# ESP32_garage_door.net
KiCad netlist of a schematic drawn in Altium Designer
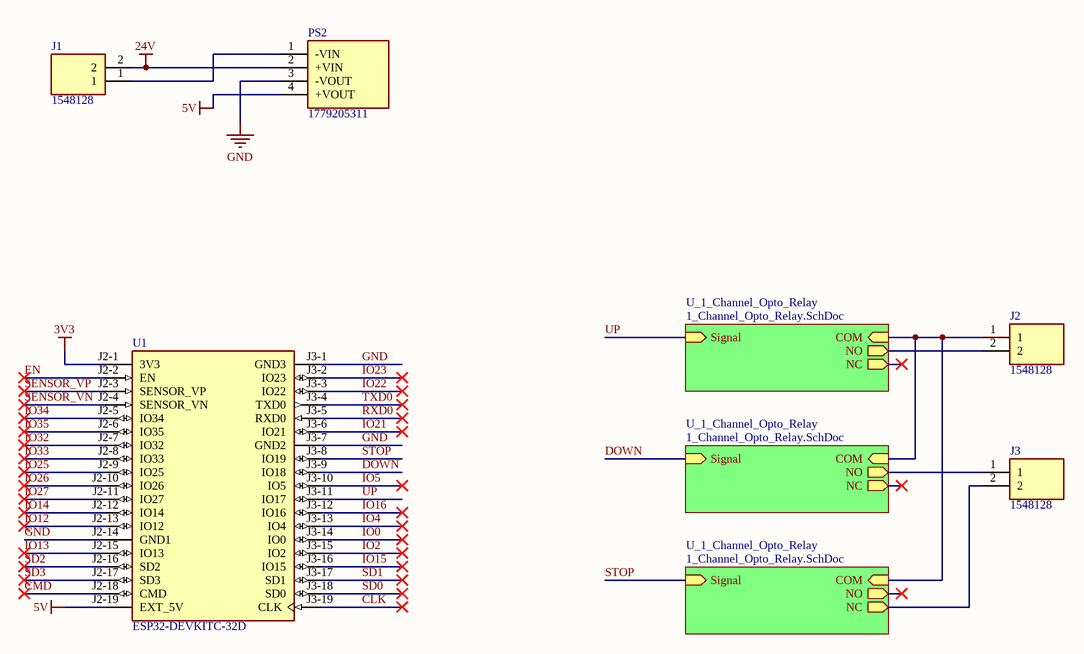
[diagram p0: ESP32_garage_door.SchDoc]

(export (version "E")
  (design (tool "Eeschema 10.0.6"))
  (components
    (comp (ref "J1")
      (value "1548128")
      (footprint "SamacSys:1548128")
      (description "Connector")
      (fields (field (name "MOUSER PART NUMBER") "651-1548128"))
      (libsource (lib "") (part "1548128_1"))
    )
    (comp (ref "J2")
      (value "1548128")
      (footprint "SamacSys:1548128")
      (description "Connector")
      (fields (field (name "MOUSER PART NUMBER") "651-1548128"))
      (libsource (lib "*") (part "1548128"))
    )
    (comp (ref "J3")
      (value "1548128")
      (footprint "SamacSys:1548128")
      (description "Connector")
      (fields (field (name "MOUSER PART NUMBER") "651-1548128"))
      (libsource (lib "*") (part "1548128"))
    )
    (comp (ref "PS2")
      (value "1779205311")
      (footprint "SamacSys:1779205311")
      (description "Power Supply")
      (libsource (lib "*") (part "1779205311"))
    )
    (comp (ref "U1")
      (value "ESP32-DEVKITC-32D")
      (footprint "MODULE_ESP32-DEVKITC-32D")
      (description "WiFi Development Tools (802.11) ESP32 General Development Kit, ESP32-WROOM-32D on the board")
      (fields (field (name "MF") "Espressif Systems"))
      (libsource (lib "Lukas Jensch") (part "ESP32-DEVKITC-32D"))
    )
  )
  (nets
    (net (code "1") (name "/CLK") (class "Default")
      (node (ref "U1") (pin "J3-19") (pinfunction "CLK_J3-19") (pintype "input+no_connect"))
    )
    (net (code "2") (name "/CMD") (class "Default")
      (node (ref "U1") (pin "J2-18") (pinfunction "CMD_J2-18") (pintype "bidirectional+no_connect"))
    )
    (net (code "3") (name "/COM") (class "Default")
      (node (ref "J2") (pin "1") (pinfunction "1_1") (pintype "passive"))
    )
    (net (code "4") (name "/DOWN") (class "Default")
      (node (ref "U1") (pin "J3-9") (pinfunction "IO18_J3-9") (pintype "bidirectional"))
    )
    (net (code "5") (name "/EN") (class "Default")
      (node (ref "U1") (pin "J2-2") (pinfunction "EN_J2-2") (pintype "input+no_connect"))
    )
    (net (code "6") (name "/IO0") (class "Default")
      (node (ref "U1") (pin "J3-14") (pinfunction "IO0_J3-14") (pintype "bidirectional+no_connect"))
    )
    (net (code "7") (name "/IO2") (class "Default")
      (node (ref "U1") (pin "J3-15") (pinfunction "IO2_J3-15") (pintype "bidirectional+no_connect"))
    )
    (net (code "8") (name "/IO4") (class "Default")
      (node (ref "U1") (pin "J3-13") (pinfunction "IO4_J3-13") (pintype "bidirectional+no_connect"))
    )
    (net (code "9") (name "/IO5") (class "Default")
      (node (ref "U1") (pin "J3-10") (pinfunction "IO5_J3-10") (pintype "bidirectional+no_connect"))
    )
    (net (code "10") (name "/IO12") (class "Default")
      (node (ref "U1") (pin "J2-13") (pinfunction "IO12_J2-13") (pintype "bidirectional+no_connect"))
    )
    (net (code "11") (name "/IO13") (class "Default")
      (node (ref "U1") (pin "J2-15") (pinfunction "IO13_J2-15") (pintype "bidirectional+no_connect"))
    )
    (net (code "12") (name "/IO14") (class "Default")
      (node (ref "U1") (pin "J2-12") (pinfunction "IO14_J2-12") (pintype "bidirectional+no_connect"))
    )
    (net (code "13") (name "/IO15") (class "Default")
      (node (ref "U1") (pin "J3-16") (pinfunction "IO15_J3-16") (pintype "bidirectional+no_connect"))
    )
    (net (code "14") (name "/IO16") (class "Default")
      (node (ref "U1") (pin "J3-12") (pinfunction "IO16_J3-12") (pintype "bidirectional+no_connect"))
    )
    (net (code "15") (name "/IO21") (class "Default")
      (node (ref "U1") (pin "J3-6") (pinfunction "IO21_J3-6") (pintype "bidirectional+no_connect"))
    )
    (net (code "16") (name "/IO22") (class "Default")
      (node (ref "U1") (pin "J3-3") (pinfunction "IO22_J3-3") (pintype "bidirectional+no_connect"))
    )
    (net (code "17") (name "/IO23") (class "Default")
      (node (ref "U1") (pin "J3-2") (pinfunction "IO23_J3-2") (pintype "bidirectional+no_connect"))
    )
    (net (code "18") (name "/IO25") (class "Default")
      (node (ref "U1") (pin "J2-9") (pinfunction "IO25_J2-9") (pintype "bidirectional+no_connect"))
    )
    (net (code "19") (name "/IO26") (class "Default")
      (node (ref "U1") (pin "J2-10") (pinfunction "IO26_J2-10") (pintype "bidirectional+no_connect"))
    )
    (net (code "20") (name "/IO27") (class "Default")
      (node (ref "U1") (pin "J2-11") (pinfunction "IO27_J2-11") (pintype "bidirectional+no_connect"))
    )
    (net (code "21") (name "/IO32") (class "Default")
      (node (ref "U1") (pin "J2-7") (pinfunction "IO32_J2-7") (pintype "bidirectional+no_connect"))
    )
    (net (code "22") (name "/IO33") (class "Default")
      (node (ref "U1") (pin "J2-8") (pinfunction "IO33_J2-8") (pintype "bidirectional+no_connect"))
    )
    (net (code "23") (name "/IO34") (class "Default")
      (node (ref "U1") (pin "J2-5") (pinfunction "IO34_J2-5") (pintype "bidirectional+no_connect"))
    )
    (net (code "24") (name "/IO35") (class "Default")
      (node (ref "U1") (pin "J2-6") (pinfunction "IO35_J2-6") (pintype "bidirectional+no_connect"))
    )
    (net (code "25") (name "/NC") (class "Default")
      (node (ref "J3") (pin "2") (pinfunction "2_2") (pintype "passive"))
    )
    (net (code "28") (name "/NO") (class "Default")
      (node (ref "J3") (pin "1") (pinfunction "1_1") (pintype "passive"))
    )
    (net (code "29") (name "/NO_1") (class "Default")
      (node (ref "J2") (pin "2") (pinfunction "2_2") (pintype "passive"))
    )
    (net (code "31") (name "/RXD0") (class "Default")
      (node (ref "U1") (pin "J3-5") (pinfunction "RXD0_J3-5") (pintype "input+no_connect"))
    )
    (net (code "32") (name "/SD0") (class "Default")
      (node (ref "U1") (pin "J3-18") (pinfunction "SD0_J3-18") (pintype "bidirectional+no_connect"))
    )
    (net (code "33") (name "/SD1") (class "Default")
      (node (ref "U1") (pin "J3-17") (pinfunction "SD1_J3-17") (pintype "bidirectional+no_connect"))
    )
    (net (code "34") (name "/SD2") (class "Default")
      (node (ref "U1") (pin "J2-16") (pinfunction "SD2_J2-16") (pintype "bidirectional+no_connect"))
    )
    (net (code "35") (name "/SD3") (class "Default")
      (node (ref "U1") (pin "J2-17") (pinfunction "SD3_J2-17") (pintype "bidirectional+no_connect"))
    )
    (net (code "36") (name "/SENSOR_VN") (class "Default")
      (node (ref "U1") (pin "J2-4") (pinfunction "SENSOR_VN_J2-4") (pintype "input+no_connect"))
    )
    (net (code "37") (name "/SENSOR_VP") (class "Default")
      (node (ref "U1") (pin "J2-3") (pinfunction "SENSOR_VP_J2-3") (pintype "input+no_connect"))
    )
    (net (code "38") (name "/STOP") (class "Default")
      (node (ref "U1") (pin "J3-8") (pinfunction "IO19_J3-8") (pintype "bidirectional"))
    )
    (net (code "39") (name "/TXD0") (class "Default")
      (node (ref "U1") (pin "J3-4") (pinfunction "TXD0_J3-4") (pintype "output+no_connect"))
    )
    (net (code "40") (name "/UP") (class "Default")
      (node (ref "U1") (pin "J3-11") (pinfunction "IO17_J3-11") (pintype "bidirectional"))
    )
    (net (code "41") (name "3V3") (class "Default")
      (node (ref "U1") (pin "J2-1") (pinfunction "3V3_J2-1") (pintype "power_in"))
    )
    (net (code "42") (name "5V") (class "Default")
      (node (ref "PS2") (pin "4") (pinfunction "+VOUT_4") (pintype "passive"))
      (node (ref "U1") (pin "J2-19") (pinfunction "EXT_5V_J2-19") (pintype "power_in"))
    )
    (net (code "43") (name "24V") (class "Default")
      (node (ref "J1") (pin "2") (pinfunction "2_2") (pintype "passive"))
      (node (ref "PS2") (pin "2") (pinfunction "+VIN_2") (pintype "passive"))
    )
    (net (code "44") (name "GND") (class "Default")
      (node (ref "PS2") (pin "3") (pinfunction "-VOUT_3") (pintype "passive"))
      (node (ref "U1") (pin "J2-14") (pinfunction "GND1_J2-14") (pintype "power_in"))
      (node (ref "U1") (pin "J3-1") (pinfunction "GND3_J3-1") (pintype "power_in"))
      (node (ref "U1") (pin "J3-7") (pinfunction "GND2_J3-7") (pintype "power_in"))
    )
    (net (code "45") (name "Net-(PS2--VIN)") (class "Default")
      (node (ref "J1") (pin "1") (pinfunction "1_1") (pintype "passive"))
      (node (ref "PS2") (pin "1") (pinfunction "-VIN_1") (pintype "passive"))
    )
  )
)
